# BackUp.net
KiCad netlist of a schematic drawn in Altium Designer
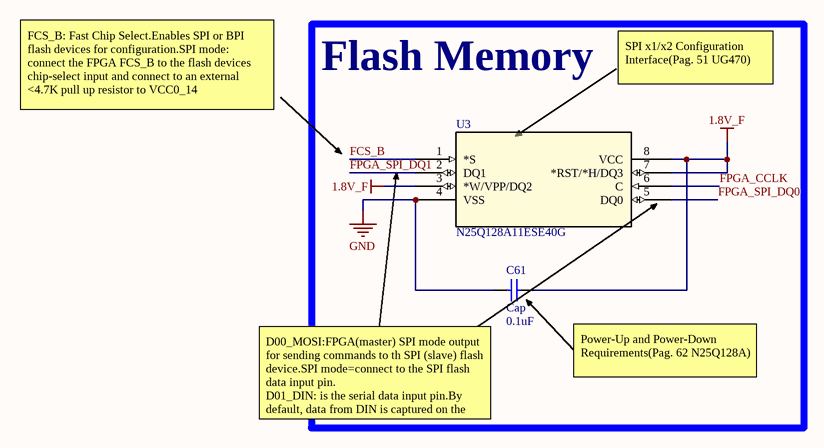
[diagram p0: BackUp.SchDoc]

(export (version "E")
  (design (tool "Eeschema 10.0.6"))
  (components
    (comp (ref "C61")
      (value "Cap")
      (footprint "MurataCapacitor:GRM0402MurataCap")
      (description "Capacitor")
      (fields
        (field (name "ALTIUM_VALUE") "0.1uF")
        (field (name "MANUFACTURER") "Murata")
        (field (name "TOLERANCE") "10%")
      )
      (libsource (lib "Miscellaneous Devices") (part "Cap"))
    )
    (comp (ref "U3")
      (value "N25Q128A11ESE40G")
      (footprint "MIC-SOP2-8-SE")
      (description "Flash Memory")
      (fields
        (field (name "MANUFACTURER") "Micron")
        (field (name "COPYRIGHT") "Copyright (C) 2015 Accelerated Designs. All rights reserved")
      )
      (libsource (lib "N25Q128A_SOP8") (part "N25Q128A11ESE40G"))
    )
  )
  (nets
    (net (code "1") (name "/FCS_B") (class "Default")
      (node (ref "U3") (pin "1") (pinfunction "*S_1") (pintype "input"))
    )
    (net (code "2") (name "/FPGA_CCLK") (class "Default")
      (node (ref "U3") (pin "6") (pinfunction "C_6") (pintype "input"))
    )
    (net (code "3") (name "/FPGA_SPI_DQ0") (class "Default")
      (node (ref "U3") (pin "5") (pinfunction "DQ0_5") (pintype "bidirectional"))
    )
    (net (code "4") (name "/FPGA_SPI_DQ1") (class "Default")
      (node (ref "U3") (pin "2") (pinfunction "DQ1_2") (pintype "bidirectional"))
    )
    (net (code "5") (name "1.8V_F") (class "Default")
      (node (ref "C61") (pin "1") (pinfunction "1_1") (pintype "passive"))
      (node (ref "U3") (pin "3") (pinfunction "*W/VPP/DQ2_3") (pintype "bidirectional"))
      (node (ref "U3") (pin "7") (pinfunction "*RST/*H/DQ3_7") (pintype "bidirectional"))
      (node (ref "U3") (pin "8") (pinfunction "VCC_8") (pintype "power_in"))
    )
    (net (code "6") (name "GND") (class "Default")
      (node (ref "C61") (pin "2") (pinfunction "2_2") (pintype "passive"))
      (node (ref "U3") (pin "4") (pinfunction "VSS_4") (pintype "power_in"))
    )
  )
)
